# power.net
KiCad netlist of a schematic drawn in EAGLE
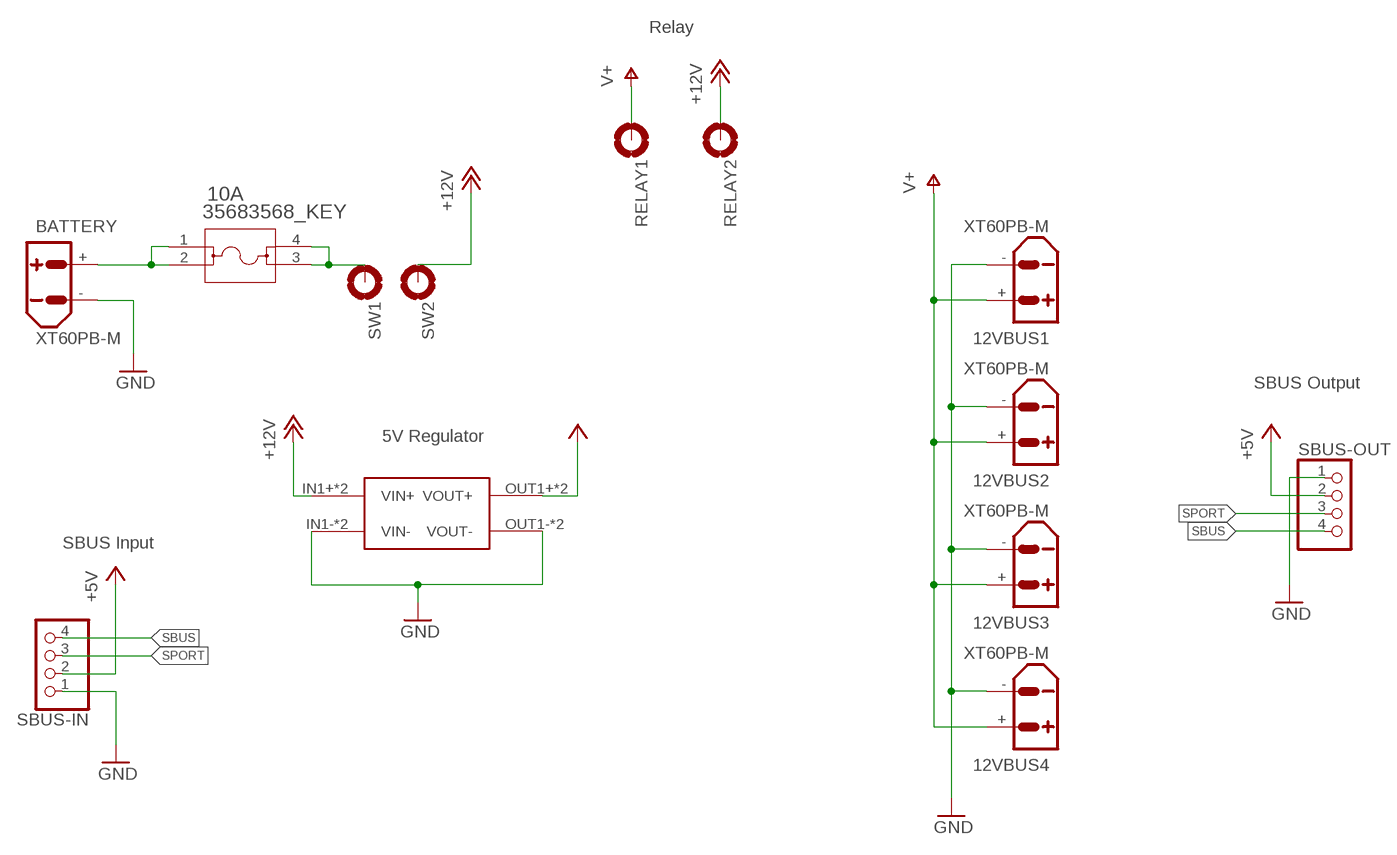
[diagram p0: schematic, sheet 1]

(export (version "E")
  (design (tool "Eeschema 10.0.6"))
  (components
    (comp (ref "10A")
      (value "35683568_KEY")
      (footprint "eagle-import:3568_KEY")
      (fields
        (field (name "MANUFACTURER_PART_NUMBER") "3568")
        (field (name "COPYRIGHT") "Copyright (C) 2023 Ultra Librarian. All rights reserved.")
      )
      (libsource (lib "eagle-import") (part "35683568_KEY"))
    )
    (comp (ref "12VBUS1")
      (value "XT60PB-M")
      (footprint "eagle-import:XT60PB-M")
      (libsource (lib "eagle-import") (part "XT60PB-M"))
    )
    (comp (ref "12VBUS2")
      (value "XT60PB-M")
      (footprint "eagle-import:XT60PB-M")
      (libsource (lib "eagle-import") (part "XT60PB-M"))
    )
    (comp (ref "12VBUS3")
      (value "XT60PB-M")
      (footprint "eagle-import:XT60PB-M")
      (libsource (lib "eagle-import") (part "XT60PB-M"))
    )
    (comp (ref "12VBUS4")
      (value "XT60PB-M")
      (footprint "eagle-import:XT60PB-M")
      (libsource (lib "eagle-import") (part "XT60PB-M"))
    )
    (comp (ref "BATTERY")
      (value "XT60PB-M")
      (footprint "eagle-import:XT60PB-M")
      (libsource (lib "eagle-import") (part "XT60PB-M"))
    )
    (comp (ref "RELAY1")
      (value "MOUNT-PAD-ROUND2.8")
      (footprint "eagle-import:2,8-PAD")
      (libsource (lib "eagle-import") (part "MOUNT-PAD-ROUND2.8"))
    )
    (comp (ref "RELAY2")
      (value "MOUNT-PAD-ROUND2.8")
      (footprint "eagle-import:2,8-PAD")
      (libsource (lib "eagle-import") (part "MOUNT-PAD-ROUND2.8"))
    )
    (comp (ref "SBUS-IN")
      (value "PINHD-1X4")
      (footprint "eagle-import:1X04")
      (libsource (lib "eagle-import") (part "PINHD-1X4"))
    )
    (comp (ref "SBUS-OUT")
      (value "PINHD-1X4")
      (footprint "eagle-import:1X04")
      (libsource (lib "eagle-import") (part "PINHD-1X4"))
    )
    (comp (ref "SW1")
      (value "MOUNT-PAD-ROUND2.8")
      (footprint "eagle-import:2,8-PAD")
      (libsource (lib "eagle-import") (part "MOUNT-PAD-ROUND2.8"))
    )
    (comp (ref "SW2")
      (value "MOUNT-PAD-ROUND2.8")
      (footprint "eagle-import:2,8-PAD")
      (libsource (lib "eagle-import") (part "MOUNT-PAD-ROUND2.8"))
    )
    (comp (ref "U$2")
      (value "MP1584")
      (footprint "eagle-import:DC-BRICK")
      (libsource (lib "eagle-import") (part "MP1584"))
    )
  )
  (nets
    (net (code "1") (name "+5V") (class "Default")
      (node (ref "SBUS-IN") (pin "2") (pinfunction "2_2") (pintype "passive"))
      (node (ref "SBUS-OUT") (pin "2") (pinfunction "2_2") (pintype "passive"))
      (node (ref "U$2") (pin "OUT1+") (pinfunction "VOUT+_OUT1+") (pintype "output"))
      (node (ref "U$2") (pin "OUT2+") (pinfunction "VOUT+_OUT2+") (pintype "output"))
    )
    (net (code "2") (name "+12V") (class "Default")
      (node (ref "RELAY2") (pin "B2,8") (pinfunction "MOUNT_B2,8") (pintype "passive"))
      (node (ref "SW2") (pin "B2,8") (pinfunction "MOUNT_B2,8") (pintype "passive"))
      (node (ref "U$2") (pin "IN1+") (pinfunction "VIN+_IN1+") (pintype "input"))
      (node (ref "U$2") (pin "IN2+") (pinfunction "VIN+_IN2+") (pintype "input"))
    )
    (net (code "3") (name "GND") (class "Default")
      (node (ref "12VBUS1") (pin "-") (pinfunction "-_-") (pintype "power_in"))
      (node (ref "12VBUS2") (pin "-") (pinfunction "-_-") (pintype "power_in"))
      (node (ref "12VBUS3") (pin "-") (pinfunction "-_-") (pintype "power_in"))
      (node (ref "12VBUS4") (pin "-") (pinfunction "-_-") (pintype "power_in"))
      (node (ref "BATTERY") (pin "-") (pinfunction "-_-") (pintype "power_in"))
      (node (ref "SBUS-IN") (pin "1") (pinfunction "1_1") (pintype "passive"))
      (node (ref "SBUS-OUT") (pin "1") (pinfunction "1_1") (pintype "passive"))
      (node (ref "U$2") (pin "IN1-") (pinfunction "VIN-_IN1-") (pintype "input"))
      (node (ref "U$2") (pin "IN2-") (pinfunction "VIN-_IN2-") (pintype "input"))
      (node (ref "U$2") (pin "OUT1-") (pinfunction "VOUT-_OUT1-") (pintype "output"))
      (node (ref "U$2") (pin "OUT2-") (pinfunction "VOUT-_OUT2-") (pintype "output"))
    )
    (net (code "4") (name "Net-(10A-Pad1)") (class "Default")
      (node (ref "10A") (pin "1") (pinfunction "1_1") (pintype "passive"))
      (node (ref "10A") (pin "2") (pinfunction "2_2") (pintype "passive"))
      (node (ref "BATTERY") (pin "+") (pinfunction "+_+") (pintype "power_in"))
    )
    (net (code "5") (name "Net-(SW1-MOUNT)") (class "Default")
      (node (ref "10A") (pin "3") (pinfunction "3_3") (pintype "passive"))
      (node (ref "10A") (pin "4") (pinfunction "4_4") (pintype "passive"))
      (node (ref "SW1") (pin "B2,8") (pinfunction "MOUNT_B2,8") (pintype "passive"))
    )
    (net (code "6") (name "SBUS") (class "Default")
      (node (ref "SBUS-IN") (pin "4") (pinfunction "4_4") (pintype "passive"))
      (node (ref "SBUS-OUT") (pin "4") (pinfunction "4_4") (pintype "passive"))
    )
    (net (code "7") (name "SPORT") (class "Default")
      (node (ref "SBUS-IN") (pin "3") (pinfunction "3_3") (pintype "passive"))
      (node (ref "SBUS-OUT") (pin "3") (pinfunction "3_3") (pintype "passive"))
    )
    (net (code "8") (name "V+") (class "Default")
      (node (ref "12VBUS1") (pin "+") (pinfunction "+_+") (pintype "power_in"))
      (node (ref "12VBUS2") (pin "+") (pinfunction "+_+") (pintype "power_in"))
      (node (ref "12VBUS3") (pin "+") (pinfunction "+_+") (pintype "power_in"))
      (node (ref "12VBUS4") (pin "+") (pinfunction "+_+") (pintype "power_in"))
      (node (ref "RELAY1") (pin "B2,8") (pinfunction "MOUNT_B2,8") (pintype "passive"))
    )
  )
)
